# Opto_Testbench.net
KiCad netlist of a schematic drawn in EAGLE
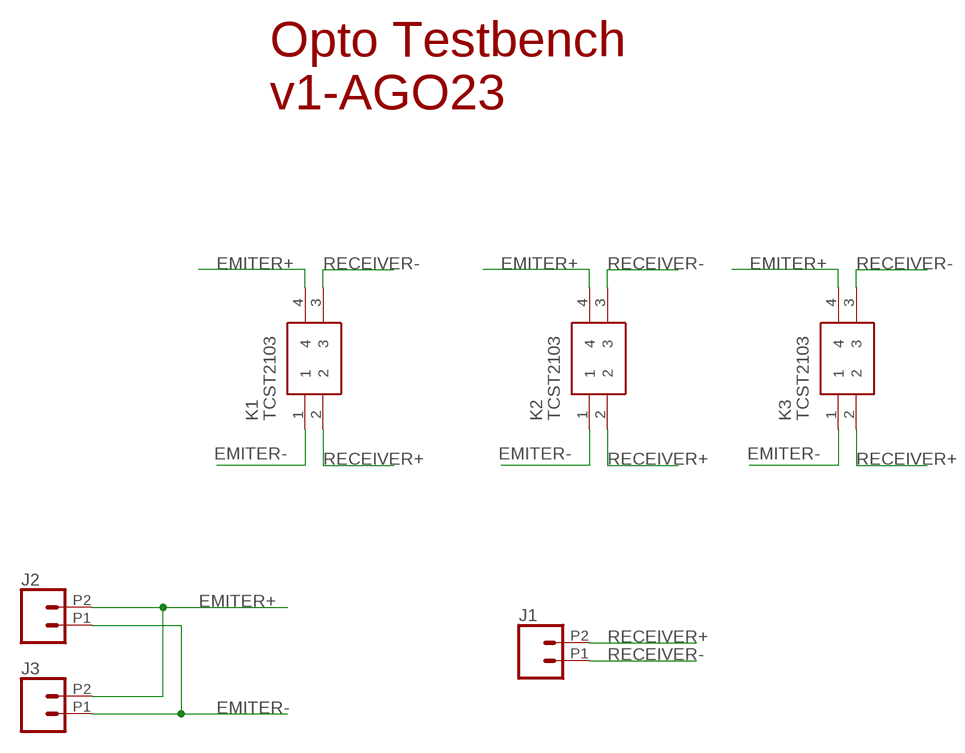
[diagram p0: schematic, sheet 1]

(export (version "E")
  (design (tool "Eeschema 10.0.6"))
  (components
    (comp (ref "J1")
      (value "CONN_022.54MM_SCREWTERM")
      (footprint "eagle-import:1X02_2.54_SCREWTERM")
      (libsource (lib "eagle-import") (part "CONN_022.54MM_SCREWTERM"))
    )
    (comp (ref "J2")
      (value "CONN_022.54MM_SCREWTERM")
      (footprint "eagle-import:1X02_2.54_SCREWTERM")
      (libsource (lib "eagle-import") (part "CONN_022.54MM_SCREWTERM"))
    )
    (comp (ref "J3")
      (value "CONN_022.54MM_SCREWTERM")
      (footprint "eagle-import:1X02_2.54_SCREWTERM")
      (libsource (lib "eagle-import") (part "CONN_022.54MM_SCREWTERM"))
    )
    (comp (ref "K1")
      (value "TCST2103")
      (footprint "eagle-import:DIPS254W40P760L2450H1110Q4N")
      (fields (field (name "MOUSER_PART_NUMBER") "782-TCST2103"))
      (libsource (lib "eagle-import") (part "TCST2103"))
    )
    (comp (ref "K2")
      (value "TCST2103")
      (footprint "eagle-import:DIPS254W40P760L2450H1110Q4N")
      (fields (field (name "MOUSER_PART_NUMBER") "782-TCST2103"))
      (libsource (lib "eagle-import") (part "TCST2103"))
    )
    (comp (ref "K3")
      (value "TCST2103")
      (footprint "eagle-import:DIPS254W40P760L2450H1110Q4N")
      (fields (field (name "MOUSER_PART_NUMBER") "782-TCST2103"))
      (libsource (lib "eagle-import") (part "TCST2103"))
    )
  )
  (nets
    (net (code "1") (name "/EMITER+") (class "Default")
      (node (ref "J2") (pin "P2") (pinfunction "2_P2") (pintype "passive"))
      (node (ref "J3") (pin "P2") (pinfunction "2_P2") (pintype "passive"))
      (node (ref "K1") (pin "4") (pinfunction "4_4") (pintype "bidirectional"))
      (node (ref "K2") (pin "4") (pinfunction "4_4") (pintype "bidirectional"))
      (node (ref "K3") (pin "4") (pinfunction "4_4") (pintype "bidirectional"))
    )
    (net (code "2") (name "/EMITER-") (class "Default")
      (node (ref "J2") (pin "P1") (pinfunction "1_P1") (pintype "passive"))
      (node (ref "J3") (pin "P1") (pinfunction "1_P1") (pintype "passive"))
      (node (ref "K1") (pin "1") (pinfunction "1_1") (pintype "bidirectional"))
      (node (ref "K2") (pin "1") (pinfunction "1_1") (pintype "bidirectional"))
      (node (ref "K3") (pin "1") (pinfunction "1_1") (pintype "bidirectional"))
    )
    (net (code "3") (name "/RECEIVER+") (class "Default")
      (node (ref "J1") (pin "P2") (pinfunction "2_P2") (pintype "passive"))
      (node (ref "K1") (pin "2") (pinfunction "2_2") (pintype "bidirectional"))
      (node (ref "K2") (pin "2") (pinfunction "2_2") (pintype "bidirectional"))
      (node (ref "K3") (pin "2") (pinfunction "2_2") (pintype "bidirectional"))
    )
    (net (code "4") (name "/RECEIVER-") (class "Default")
      (node (ref "J1") (pin "P1") (pinfunction "1_P1") (pintype "passive"))
      (node (ref "K1") (pin "3") (pinfunction "3_3") (pintype "bidirectional"))
      (node (ref "K2") (pin "3") (pinfunction "3_3") (pintype "bidirectional"))
      (node (ref "K3") (pin "3") (pinfunction "3_3") (pintype "bidirectional"))
    )
  )
)
